# STM32F2_Controller.net
KiCad netlist of a schematic drawn in EAGLE
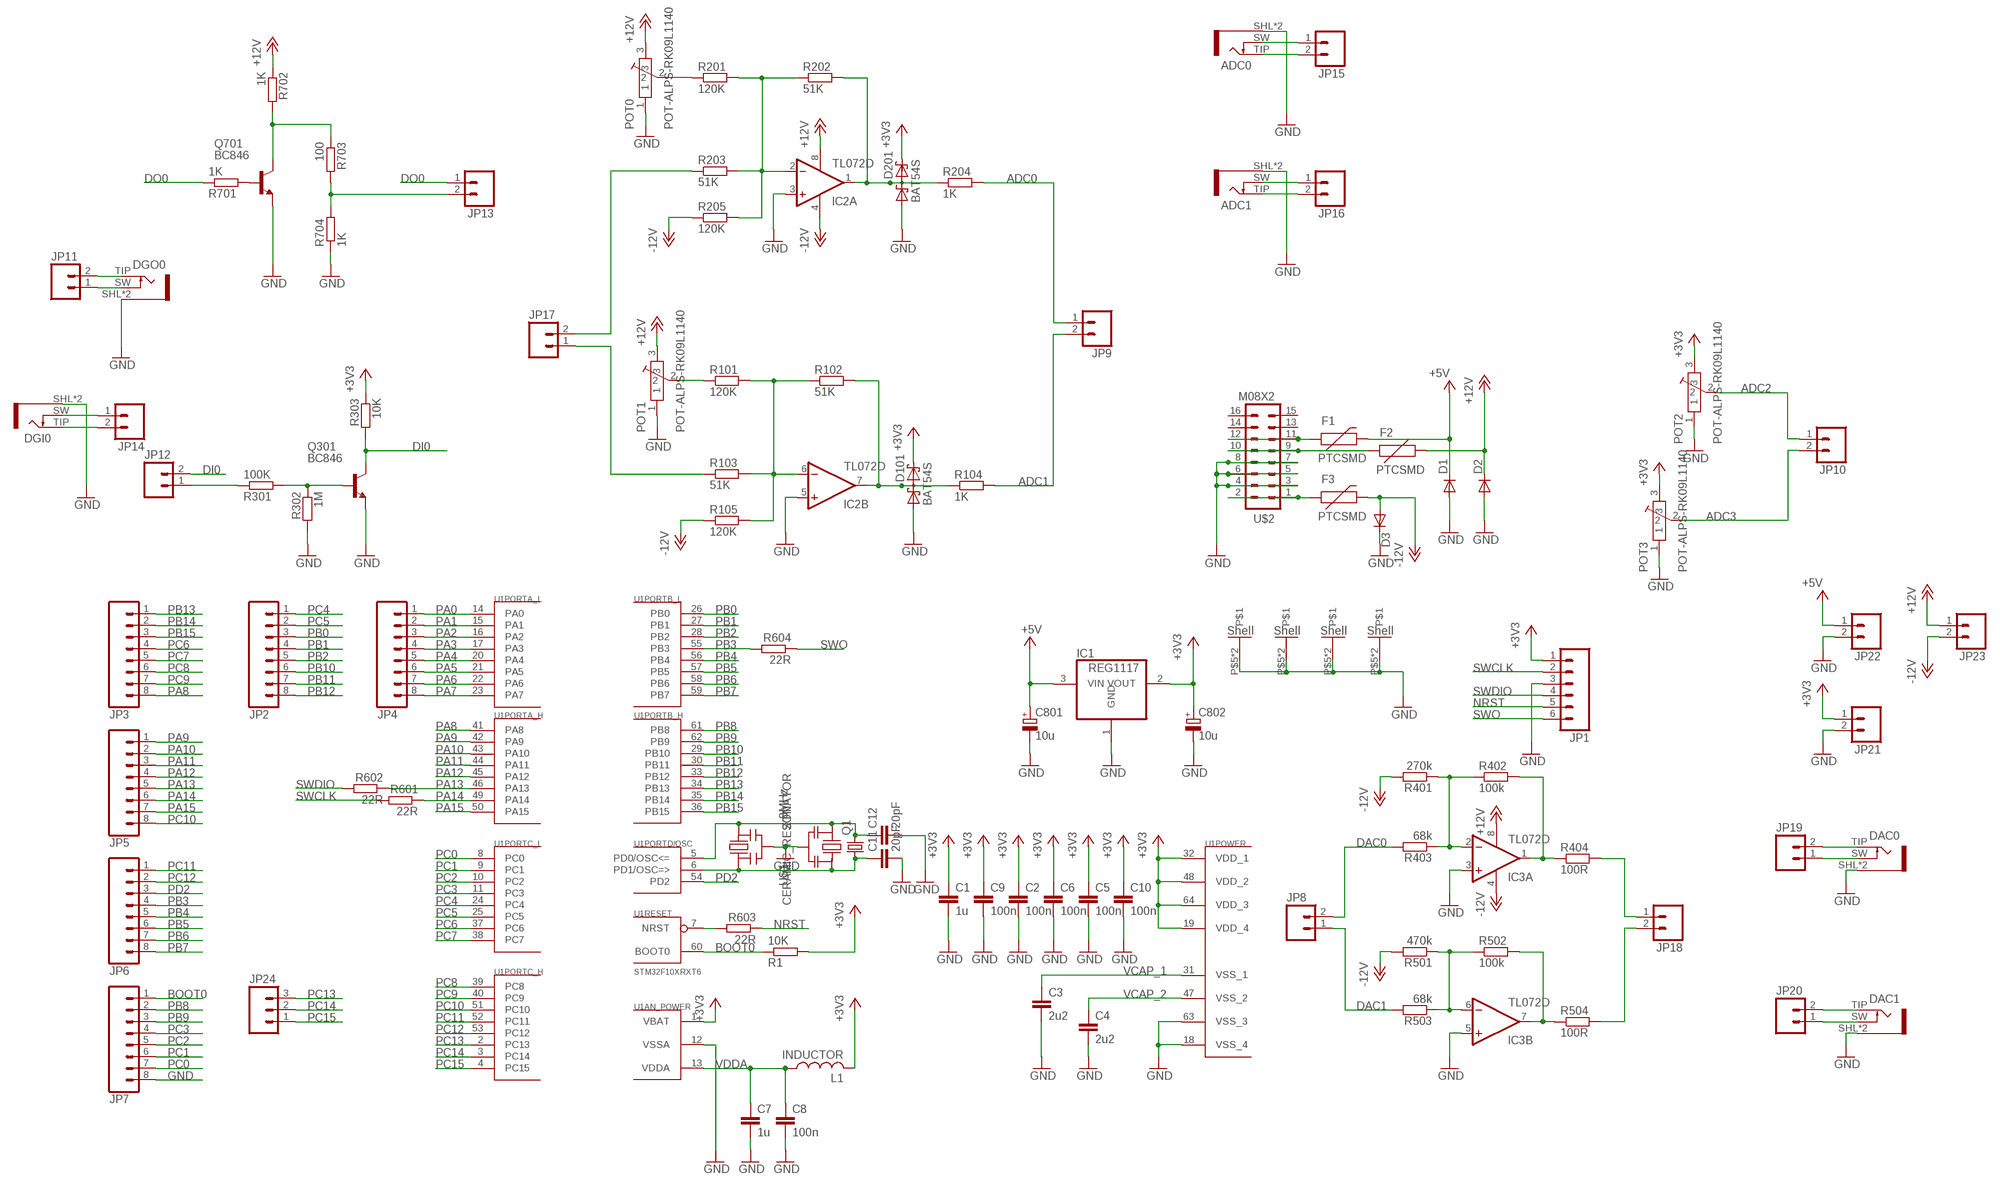
[diagram p0: schematic, sheet 1]

(export (version "E")
  (design (tool "Eeschema 10.0.6"))
  (components
    (comp (ref "ADC0")
      (value "JACK-PJ-301B")
      (footprint "eagle-import:PJ-301B")
      (libsource (lib "eagle-import") (part "JACK-PJ-301B"))
    )
    (comp (ref "ADC1")
      (value "JACK-PJ-301B")
      (footprint "eagle-import:PJ-301B")
      (libsource (lib "eagle-import") (part "JACK-PJ-301B"))
    )
    (comp (ref "C1")
      (value "1u")
      (footprint "eagle-import:C0603")
      (libsource (lib "eagle-import") (part "C-EUC0603"))
    )
    (comp (ref "C2")
      (value "100n")
      (footprint "eagle-import:C0603")
      (libsource (lib "eagle-import") (part "C-EUC0603"))
    )
    (comp (ref "C3")
      (value "2u2")
      (footprint "eagle-import:C0603")
      (libsource (lib "eagle-import") (part "C-EUC0603"))
    )
    (comp (ref "C4")
      (value "2u2")
      (footprint "eagle-import:C0603")
      (libsource (lib "eagle-import") (part "C-EUC0603"))
    )
    (comp (ref "C5")
      (value "100n")
      (footprint "eagle-import:C0603")
      (libsource (lib "eagle-import") (part "C-EUC0603"))
    )
    (comp (ref "C6")
      (value "100n")
      (footprint "eagle-import:C0603")
      (libsource (lib "eagle-import") (part "C-EUC0603"))
    )
    (comp (ref "C7")
      (value "1u")
      (footprint "eagle-import:C0603")
      (libsource (lib "eagle-import") (part "C-EUC0603"))
    )
    (comp (ref "C8")
      (value "100n")
      (footprint "eagle-import:C0603")
      (libsource (lib "eagle-import") (part "C-EUC0603"))
    )
    (comp (ref "C9")
      (value "100n")
      (footprint "eagle-import:C0603")
      (libsource (lib "eagle-import") (part "C-EUC0603"))
    )
    (comp (ref "C10")
      (value "100n")
      (footprint "eagle-import:C0603")
      (libsource (lib "eagle-import") (part "C-EUC0603"))
    )
    (comp (ref "C11")
      (value "20pF")
      (footprint "eagle-import:C0603")
      (libsource (lib "eagle-import") (part "C-EUC0603"))
    )
    (comp (ref "C12")
      (value "20pF")
      (footprint "eagle-import:C0603")
      (libsource (lib "eagle-import") (part "C-EUC0603"))
    )
    (comp (ref "C801")
      (value "10u")
      (footprint "eagle-import:PANASONIC_A")
      (libsource (lib "eagle-import") (part "CPOL-EUA"))
    )
    (comp (ref "C802")
      (value "10u")
      (footprint "eagle-import:PANASONIC_A")
      (libsource (lib "eagle-import") (part "CPOL-EUA"))
    )
    (comp (ref "D1")
      (value "DIODESMA")
      (footprint "eagle-import:SMA-DIODE")
      (libsource (lib "eagle-import") (part "DIODESMA"))
    )
    (comp (ref "D2")
      (value "DIODESMA")
      (footprint "eagle-import:SMA-DIODE")
      (libsource (lib "eagle-import") (part "DIODESMA"))
    )
    (comp (ref "D3")
      (value "DIODESMA")
      (footprint "eagle-import:SMA-DIODE")
      (libsource (lib "eagle-import") (part "DIODESMA"))
    )
    (comp (ref "D101")
      (value "BAT54S")
      (footprint "eagle-import:SOT23")
      (libsource (lib "eagle-import") (part "BAT54S"))
    )
    (comp (ref "D201")
      (value "BAT54S")
      (footprint "eagle-import:SOT23")
      (libsource (lib "eagle-import") (part "BAT54S"))
    )
    (comp (ref "DAC0")
      (value "JACK-PJ-301B")
      (footprint "eagle-import:PJ-301B")
      (libsource (lib "eagle-import") (part "JACK-PJ-301B"))
    )
    (comp (ref "DAC1")
      (value "JACK-PJ-301B")
      (footprint "eagle-import:PJ-301B")
      (libsource (lib "eagle-import") (part "JACK-PJ-301B"))
    )
    (comp (ref "DGI0")
      (value "JACK-PJ-301B")
      (footprint "eagle-import:PJ-301B")
      (libsource (lib "eagle-import") (part "JACK-PJ-301B"))
    )
    (comp (ref "DGO0")
      (value "JACK-PJ-301B")
      (footprint "eagle-import:PJ-301B")
      (libsource (lib "eagle-import") (part "JACK-PJ-301B"))
    )
    (comp (ref "F1")
      (value "PTCSMD")
      (footprint "eagle-import:PTC-1206")
      (libsource (lib "eagle-import") (part "PTCSMD"))
    )
    (comp (ref "F2")
      (value "PTCSMD")
      (footprint "eagle-import:PTC-1206")
      (libsource (lib "eagle-import") (part "PTCSMD"))
    )
    (comp (ref "F3")
      (value "PTCSMD")
      (footprint "eagle-import:PTC-1206")
      (libsource (lib "eagle-import") (part "PTCSMD"))
    )
    (comp (ref "IC1")
      (value "REG1117")
      (footprint "eagle-import:SOT223")
      (libsource (lib "eagle-import") (part "REG1117"))
    )
    (comp (ref "IC2")
      (value "TL072D")
      (footprint "eagle-import:SO08")
      (libsource (lib "eagle-import") (part "TL072D"))
    )
    (comp (ref "IC3")
      (value "TL072D")
      (footprint "eagle-import:SO08")
      (libsource (lib "eagle-import") (part "TL072D"))
    )
    (comp (ref "JP1")
      (value "M06SIP")
      (footprint "eagle-import:1X06")
      (libsource (lib "eagle-import") (part "M06SIP"))
    )
    (comp (ref "JP2")
      (value "M081X08")
      (footprint "eagle-import:1X08")
      (libsource (lib "eagle-import") (part "M081X08"))
    )
    (comp (ref "JP3")
      (value "M081X08")
      (footprint "eagle-import:1X08")
      (libsource (lib "eagle-import") (part "M081X08"))
    )
    (comp (ref "JP4")
      (value "M081X08")
      (footprint "eagle-import:1X08")
      (libsource (lib "eagle-import") (part "M081X08"))
    )
    (comp (ref "JP5")
      (value "M081X08")
      (footprint "eagle-import:1X08")
      (libsource (lib "eagle-import") (part "M081X08"))
    )
    (comp (ref "JP6")
      (value "M081X08")
      (footprint "eagle-import:1X08")
      (libsource (lib "eagle-import") (part "M081X08"))
    )
    (comp (ref "JP7")
      (value "M081X08")
      (footprint "eagle-import:1X08")
      (libsource (lib "eagle-import") (part "M081X08"))
    )
    (comp (ref "JP8")
      (value "M02PTH")
      (footprint "eagle-import:1X02")
      (libsource (lib "eagle-import") (part "M02PTH"))
    )
    (comp (ref "JP9")
      (value "M02PTH")
      (footprint "eagle-import:1X02")
      (libsource (lib "eagle-import") (part "M02PTH"))
    )
    (comp (ref "JP10")
      (value "M02PTH")
      (footprint "eagle-import:1X02")
      (libsource (lib "eagle-import") (part "M02PTH"))
    )
    (comp (ref "JP11")
      (value "M02PTH")
      (footprint "eagle-import:1X02")
      (libsource (lib "eagle-import") (part "M02PTH"))
    )
    (comp (ref "JP12")
      (value "M02PTH")
      (footprint "eagle-import:1X02")
      (libsource (lib "eagle-import") (part "M02PTH"))
    )
    (comp (ref "JP13")
      (value "M02PTH")
      (footprint "eagle-import:1X02")
      (libsource (lib "eagle-import") (part "M02PTH"))
    )
    (comp (ref "JP14")
      (value "M02PTH")
      (footprint "eagle-import:1X02")
      (libsource (lib "eagle-import") (part "M02PTH"))
    )
    (comp (ref "JP15")
      (value "M02PTH")
      (footprint "eagle-import:1X02")
      (libsource (lib "eagle-import") (part "M02PTH"))
    )
    (comp (ref "JP16")
      (value "M02PTH")
      (footprint "eagle-import:1X02")
      (libsource (lib "eagle-import") (part "M02PTH"))
    )
    (comp (ref "JP17")
      (value "M02PTH")
      (footprint "eagle-import:1X02")
      (libsource (lib "eagle-import") (part "M02PTH"))
    )
    (comp (ref "JP18")
      (value "M02PTH")
      (footprint "eagle-import:1X02")
      (libsource (lib "eagle-import") (part "M02PTH"))
    )
    (comp (ref "JP19")
      (value "M02PTH")
      (footprint "eagle-import:1X02")
      (libsource (lib "eagle-import") (part "M02PTH"))
    )
    (comp (ref "JP20")
      (value "M02PTH")
      (footprint "eagle-import:1X02")
      (libsource (lib "eagle-import") (part "M02PTH"))
    )
    (comp (ref "JP21")
      (value "M02PTH")
      (footprint "eagle-import:1X02")
      (libsource (lib "eagle-import") (part "M02PTH"))
    )
    (comp (ref "JP22")
      (value "M02PTH")
      (footprint "eagle-import:1X02")
      (libsource (lib "eagle-import") (part "M02PTH"))
    )
    (comp (ref "JP23")
      (value "M02PTH")
      (footprint "eagle-import:1X02")
      (libsource (lib "eagle-import") (part "M02PTH"))
    )
    (comp (ref "JP24")
      (value "M03PTH")
      (footprint "eagle-import:1X03")
      (libsource (lib "eagle-import") (part "M03PTH"))
    )
    (comp (ref "L1")
      (value "INDUCTOR")
      (footprint "eagle-import:0603")
      (libsource (lib "eagle-import") (part "INDUCTOR"))
    )
    (comp (ref "POT0")
      (value "POT-ALPS-RK09L1140")
      (footprint "eagle-import:POT-ALPS-RK09L1140")
      (libsource (lib "eagle-import") (part "POT-ALPS-RK09L1140"))
    )
    (comp (ref "POT1")
      (value "POT-ALPS-RK09L1140")
      (footprint "eagle-import:POT-ALPS-RK09L1140")
      (libsource (lib "eagle-import") (part "POT-ALPS-RK09L1140"))
    )
    (comp (ref "POT2")
      (value "POT-ALPS-RK09L1140")
      (footprint "eagle-import:POT-ALPS-RK09L1140")
      (libsource (lib "eagle-import") (part "POT-ALPS-RK09L1140"))
    )
    (comp (ref "POT3")
      (value "POT-ALPS-RK09L1140")
      (footprint "eagle-import:POT-ALPS-RK09L1140")
      (libsource (lib "eagle-import") (part "POT-ALPS-RK09L1140"))
    )
    (comp (ref "Q1")
      (value "CRYSTALHC49UP")
      (footprint "eagle-import:HC49UP")
      (libsource (lib "eagle-import") (part "CRYSTALHC49UP"))
    )
    (comp (ref "Q301")
      (value "BC846")
      (footprint "eagle-import:SOT23")
      (libsource (lib "eagle-import") (part "BC846"))
    )
    (comp (ref "Q701")
      (value "BC846")
      (footprint "eagle-import:SOT23")
      (libsource (lib "eagle-import") (part "BC846"))
    )
    (comp (ref "R1")
      (value "10K")
      (footprint "eagle-import:R0603")
      (libsource (lib "eagle-import") (part "R-EU_R0603"))
    )
    (comp (ref "R101")
      (value "120K")
      (footprint "eagle-import:R0603")
      (libsource (lib "eagle-import") (part "R-EU_R0603"))
    )
    (comp (ref "R102")
      (value "51K")
      (footprint "eagle-import:R0603")
      (libsource (lib "eagle-import") (part "R-EU_R0603"))
    )
    (comp (ref "R103")
      (value "51K")
      (footprint "eagle-import:R0603")
      (libsource (lib "eagle-import") (part "R-EU_R0603"))
    )
    (comp (ref "R104")
      (value "1K")
      (footprint "eagle-import:R0603")
      (libsource (lib "eagle-import") (part "R-EU_R0603"))
    )
    (comp (ref "R105")
      (value "120K")
      (footprint "eagle-import:R0603")
      (libsource (lib "eagle-import") (part "R-EU_R0603"))
    )
    (comp (ref "R201")
      (value "120K")
      (footprint "eagle-import:R0603")
      (libsource (lib "eagle-import") (part "R-EU_R0603"))
    )
    (comp (ref "R202")
      (value "51K")
      (footprint "eagle-import:R0603")
      (libsource (lib "eagle-import") (part "R-EU_R0603"))
    )
    (comp (ref "R203")
      (value "51K")
      (footprint "eagle-import:R0603")
      (libsource (lib "eagle-import") (part "R-EU_R0603"))
    )
    (comp (ref "R204")
      (value "1K")
      (footprint "eagle-import:R0603")
      (libsource (lib "eagle-import") (part "R-EU_R0603"))
    )
    (comp (ref "R205")
      (value "120K")
      (footprint "eagle-import:R0603")
      (libsource (lib "eagle-import") (part "R-EU_R0603"))
    )
    (comp (ref "R301")
      (value "100K")
      (footprint "eagle-import:R0603")
      (libsource (lib "eagle-import") (part "R-EU_R0603"))
    )
    (comp (ref "R302")
      (value "1M")
      (footprint "eagle-import:R0603")
      (libsource (lib "eagle-import") (part "R-EU_R0603"))
    )
    (comp (ref "R303")
      (value "10K")
      (footprint "eagle-import:R0603")
      (libsource (lib "eagle-import") (part "R-EU_R0603"))
    )
    (comp (ref "R401")
      (value "270k")
      (footprint "eagle-import:R0603")
      (libsource (lib "eagle-import") (part "R-EU_R0603"))
    )
    (comp (ref "R402")
      (value "100k")
      (footprint "eagle-import:R0603")
      (libsource (lib "eagle-import") (part "R-EU_R0603"))
    )
    (comp (ref "R403")
      (value "68k")
      (footprint "eagle-import:R0603")
      (libsource (lib "eagle-import") (part "R-EU_R0603"))
    )
    (comp (ref "R404")
      (value "100R")
      (footprint "eagle-import:R0603")
      (libsource (lib "eagle-import") (part "R-EU_R0603"))
    )
    (comp (ref "R501")
      (value "470k")
      (footprint "eagle-import:R0603")
      (libsource (lib "eagle-import") (part "R-EU_R0603"))
    )
    (comp (ref "R502")
      (value "100k")
      (footprint "eagle-import:R0603")
      (libsource (lib "eagle-import") (part "R-EU_R0603"))
    )
    (comp (ref "R503")
      (value "68k")
      (footprint "eagle-import:R0603")
      (libsource (lib "eagle-import") (part "R-EU_R0603"))
    )
    (comp (ref "R504")
      (value "100R")
      (footprint "eagle-import:R0603")
      (libsource (lib "eagle-import") (part "R-EU_R0603"))
    )
    (comp (ref "R601")
      (value "22R")
      (footprint "eagle-import:R0603")
      (libsource (lib "eagle-import") (part "R-EU_R0603"))
    )
    (comp (ref "R602")
      (value "22R")
      (footprint "eagle-import:R0603")
      (libsource (lib "eagle-import") (part "R-EU_R0603"))
    )
    (comp (ref "R603")
      (value "22R")
      (footprint "eagle-import:R0603")
      (libsource (lib "eagle-import") (part "R-EU_R0603"))
    )
    (comp (ref "R604")
      (value "22R")
      (footprint "eagle-import:R0603")
      (libsource (lib "eagle-import") (part "R-EU_R0603"))
    )
    (comp (ref "R701")
      (value "1K")
      (footprint "eagle-import:R0603")
      (libsource (lib "eagle-import") (part "R-EU_R0603"))
    )
    (comp (ref "R702")
      (value "1K")
      (footprint "eagle-import:R0603")
      (libsource (lib "eagle-import") (part "R-EU_R0603"))
    )
    (comp (ref "R703")
      (value "100")
      (footprint "eagle-import:R0603")
      (libsource (lib "eagle-import") (part "R-EU_R0603"))
    )
    (comp (ref "R704")
      (value "1K")
      (footprint "eagle-import:R0603")
      (libsource (lib "eagle-import") (part "R-EU_R0603"))
    )
    (comp (ref "U$1")
      (value "8MHz")
      (footprint "eagle-import:CSTCR-G")
      (libsource (lib "eagle-import") (part "CERMOSCILL-CSTCRG"))
    )
    (comp (ref "U$2")
      (value "M08X2")
      (footprint "eagle-import:2X8")
      (libsource (lib "eagle-import") (part "M08X2"))
    )
    (comp (ref "U1")
      (value "STM32F10XRXT6")
      (footprint "eagle-import:TQFP64")
      (libsource (lib "eagle-import") (part "STM32F10XRXT6"))
    )
    (comp (ref "ZTT")
      (value "CERAMIC_RESONATOR")
      (footprint "eagle-import:CSTCE_G_A")
      (libsource (lib "eagle-import") (part "CERAMIC_RESONATOR"))
    )
  )
  (nets
    (net (code "1") (name "+3V3") (class "Default")
      (node (ref "C1") (pin "1") (pinfunction "1_1") (pintype "passive"))
      (node (ref "C10") (pin "1") (pinfunction "1_1") (pintype "passive"))
      (node (ref "C2") (pin "1") (pinfunction "1_1") (pintype "passive"))
      (node (ref "C5") (pin "1") (pinfunction "1_1") (pintype "passive"))
      (node (ref "C6") (pin "1") (pinfunction "1_1") (pintype "passive"))
      (node (ref "C802") (pin "+") (pinfunction "+_+") (pintype "passive"))
      (node (ref "C9") (pin "1") (pinfunction "1_1") (pintype "passive"))
      (node (ref "D101") (pin "2") (pinfunction "C2_2") (pintype "passive"))
      (node (ref "D201") (pin "2") (pinfunction "C2_2") (pintype "passive"))
      (node (ref "IC1") (pin "2") (pinfunction "VOUT_2") (pintype "output"))
      (node (ref "JP1") (pin "1") (pinfunction "1_1") (pintype "passive"))
      (node (ref "JP21") (pin "1") (pinfunction "1_1") (pintype "passive"))
      (node (ref "L1") (pin "2") (pinfunction "2_2") (pintype "passive"))
      (node (ref "POT2") (pin "3") (pinfunction "3_3") (pintype "bidirectional"))
      (node (ref "POT3") (pin "3") (pinfunction "3_3") (pintype "bidirectional"))
      (node (ref "R1") (pin "2") (pinfunction "2_2") (pintype "passive"))
      (node (ref "R303") (pin "1") (pinfunction "1_1") (pintype "passive"))
      (node (ref "U1") (pin "1") (pinfunction "VBAT_1") (pintype "power_in"))
      (node (ref "U1") (pin "19") (pinfunction "VDD_4_19") (pintype "power_in"))
      (node (ref "U1") (pin "32") (pinfunction "VDD_1_32") (pintype "power_in"))
      (node (ref "U1") (pin "48") (pinfunction "VDD_2_48") (pintype "power_in"))
      (node (ref "U1") (pin "64") (pinfunction "VDD_3_64") (pintype "power_in"))
    )
    (net (code "2") (name "+5V") (class "Default")
      (node (ref "C801") (pin "+") (pinfunction "+_+") (pintype "passive"))
      (node (ref "D1") (pin "C") (pinfunction "C_C") (pintype "passive"))
      (node (ref "F1") (pin "2") (pinfunction "2_2") (pintype "bidirectional"))
      (node (ref "IC1") (pin "3") (pinfunction "VIN_3") (pintype "input"))
      (node (ref "JP22") (pin "1") (pinfunction "1_1") (pintype "passive"))
    )
    (net (code "3") (name "+12V") (class "Default")
      (node (ref "D2") (pin "C") (pinfunction "C_C") (pintype "passive"))
      (node (ref "F2") (pin "2") (pinfunction "2_2") (pintype "bidirectional"))
      (node (ref "IC2") (pin "8") (pinfunction "V+_8") (pintype "power_in"))
      (node (ref "IC3") (pin "8") (pinfunction "V+_8") (pintype "power_in"))
      (node (ref "JP23") (pin "1") (pinfunction "1_1") (pintype "passive"))
      (node (ref "POT0") (pin "3") (pinfunction "3_3") (pintype "bidirectional"))
      (node (ref "POT1") (pin "3") (pinfunction "3_3") (pintype "bidirectional"))
      (node (ref "R702") (pin "1") (pinfunction "1_1") (pintype "passive"))
    )
    (net (code "4") (name "-12V") (class "Default")
      (node (ref "D3") (pin "A") (pinfunction "A_A") (pintype "passive"))
      (node (ref "F3") (pin "2") (pinfunction "2_2") (pintype "bidirectional"))
      (node (ref "IC2") (pin "4") (pinfunction "V-_4") (pintype "power_in"))
      (node (ref "IC3") (pin "4") (pinfunction "V-_4") (pintype "power_in"))
      (node (ref "JP23") (pin "2") (pinfunction "2_2") (pintype "passive"))
      (node (ref "R105") (pin "1") (pinfunction "1_1") (pintype "passive"))
      (node (ref "R205") (pin "1") (pinfunction "1_1") (pintype "passive"))
      (node (ref "R401") (pin "2") (pinfunction "2_2") (pintype "passive"))
      (node (ref "R501") (pin "2") (pinfunction "2_2") (pintype "passive"))
    )
    (net (code "5") (name "/ADC0") (class "Default")
      (node (ref "JP9") (pin "1") (pinfunction "1_1") (pintype "passive"))
      (node (ref "R204") (pin "2") (pinfunction "2_2") (pintype "passive"))
    )
    (net (code "6") (name "/ADC1") (class "Default")
      (node (ref "JP9") (pin "2") (pinfunction "2_2") (pintype "passive"))
      (node (ref "R104") (pin "2") (pinfunction "2_2") (pintype "passive"))
    )
    (net (code "7") (name "/ADC2") (class "Default")
      (node (ref "JP10") (pin "1") (pinfunction "1_1") (pintype "passive"))
      (node (ref "POT2") (pin "2") (pinfunction "2_2") (pintype "bidirectional"))
    )
    (net (code "8") (name "/ADC3") (class "Default")
      (node (ref "JP10") (pin "2") (pinfunction "2_2") (pintype "passive"))
      (node (ref "POT3") (pin "2") (pinfunction "2_2") (pintype "bidirectional"))
    )
    (net (code "9") (name "/BOOT0") (class "Default")
      (node (ref "JP7") (pin "1") (pinfunction "1_1") (pintype "passive"))
      (node (ref "R1") (pin "1") (pinfunction "1_1") (pintype "passive"))
      (node (ref "U1") (pin "60") (pinfunction "BOOT0_60") (pintype "input"))
    )
    (net (code "10") (name "/DAC0") (class "Default")
      (node (ref "JP8") (pin "2") (pinfunction "2_2") (pintype "passive"))
      (node (ref "R403") (pin "2") (pinfunction "2_2") (pintype "passive"))
    )
    (net (code "11") (name "/DAC1") (class "Default")
      (node (ref "JP8") (pin "1") (pinfunction "1_1") (pintype "passive"))
      (node (ref "R503") (pin "2") (pinfunction "2_2") (pintype "passive"))
    )
    (net (code "12") (name "/DI0") (class "Default")
      (node (ref "JP12") (pin "2") (pinfunction "2_2") (pintype "passive"))
      (node (ref "Q301") (pin "3") (pinfunction "C_3") (pintype "passive"))
      (node (ref "R303") (pin "2") (pinfunction "2_2") (pintype "passive"))
    )
    (net (code "13") (name "/DO0") (class "Default")
      (node (ref "JP13") (pin "1") (pinfunction "1_1") (pintype "passive"))
      (node (ref "R701") (pin "1") (pinfunction "1_1") (pintype "passive"))
    )
    (net (code "14") (name "/NRST") (class "Default")
      (node (ref "JP1") (pin "5") (pinfunction "5_5") (pintype "passive"))
      (node (ref "R603") (pin "1") (pinfunction "1_1") (pintype "passive"))
    )
    (net (code "15") (name "/PA0") (class "Default")
      (node (ref "JP4") (pin "1") (pinfunction "1_1") (pintype "passive"))
      (node (ref "U1") (pin "14") (pinfunction "PA0_14") (pintype "bidirectional"))
    )
    (net (code "16") (name "/PA1") (class "Default")
      (node (ref "JP4") (pin "2") (pinfunction "2_2") (pintype "passive"))
      (node (ref "U1") (pin "15") (pinfunction "PA1_15") (pintype "bidirectional"))
    )
    (net (code "17") (name "/PA2") (class "Default")
      (node (ref "JP4") (pin "3") (pinfunction "3_3") (pintype "passive"))
      (node (ref "U1") (pin "16") (pinfunction "PA2_16") (pintype "bidirectional"))
    )
    (net (code "18") (name "/PA3") (class "Default")
      (node (ref "JP4") (pin "4") (pinfunction "4_4") (pintype "passive"))
      (node (ref "U1") (pin "17") (pinfunction "PA3_17") (pintype "bidirectional"))
    )
    (net (code "19") (name "/PA4") (class "Default")
      (node (ref "JP4") (pin "5") (pinfunction "5_5") (pintype "passive"))
      (node (ref "U1") (pin "20") (pinfunction "PA4_20") (pintype "bidirectional"))
    )
    (net (code "20") (name "/PA5") (class "Default")
      (node (ref "JP4") (pin "6") (pinfunction "6_6") (pintype "passive"))
      (node (ref "U1") (pin "21") (pinfunction "PA5_21") (pintype "bidirectional"))
    )
    (net (code "21") (name "/PA6") (class "Default")
      (node (ref "JP4") (pin "7") (pinfunction "7_7") (pintype "passive"))
      (node (ref "U1") (pin "22") (pinfunction "PA6_22") (pintype "bidirectional"))
    )
    (net (code "22") (name "/PA7") (class "Default")
      (node (ref "JP4") (pin "8") (pinfunction "8_8") (pintype "passive"))
      (node (ref "U1") (pin "23") (pinfunction "PA7_23") (pintype "bidirectional"))
    )
    (net (code "23") (name "/PA8") (class "Default")
      (node (ref "JP3") (pin "8") (pinfunction "8_8") (pintype "passive"))
      (node (ref "U1") (pin "41") (pinfunction "PA8_41") (pintype "bidirectional"))
    )
    (net (code "24") (name "/PA9") (class "Default")
      (node (ref "JP5") (pin "1") (pinfunction "1_1") (pintype "passive"))
      (node (ref "U1") (pin "42") (pinfunction "PA9_42") (pintype "bidirectional"))
    )
    (net (code "25") (name "/PA10") (class "Default")
      (node (ref "JP5") (pin "2") (pinfunction "2_2") (pintype "passive"))
      (node (ref "U1") (pin "43") (pinfunction "PA10_43") (pintype "bidirectional"))
    )
    (net (code "26") (name "/PA11") (class "Default")
      (node (ref "JP5") (pin "3") (pinfunction "3_3") (pintype "passive"))
      (node (ref "U1") (pin "44") (pinfunction "PA11_44") (pintype "bidirectional"))
    )
    (net (code "27") (name "/PA12") (class "Default")
      (node (ref "JP5") (pin "4") (pinfunction "4_4") (pintype "passive"))
      (node (ref "U1") (pin "45") (pinfunction "PA12_45") (pintype "bidirectional"))
    )
    (net (code "28") (name "/PA13") (class "Default")
      (node (ref "JP5") (pin "5") (pinfunction "5_5") (pintype "passive"))
      (node (ref "R602") (pin "1") (pinfunction "1_1") (pintype "passive"))
      (node (ref "U1") (pin "46") (pinfunction "PA13_46") (pintype "bidirectional"))
    )
    (net (code "29") (name "/PA14") (class "Default")
      (node (ref "JP5") (pin "6") (pinfunction "6_6") (pintype "passive"))
      (node (ref "R601") (pin "1") (pinfunction "1_1") (pintype "passive"))
      (node (ref "U1") (pin "49") (pinfunction "PA14_49") (pintype "bidirectional"))
    )
    (net (code "30") (name "/PA15") (class "Default")
      (node (ref "JP5") (pin "7") (pinfunction "7_7") (pintype "passive"))
      (node (ref "U1") (pin "50") (pinfunction "PA15_50") (pintype "bidirectional"))
    )
    (net (code "31") (name "/PB0") (class "Default")
      (node (ref "JP2") (pin "3") (pinfunction "3_3") (pintype "passive"))
      (node (ref "U1") (pin "26") (pinfunction "PB0_26") (pintype "bidirectional"))
    )
    (net (code "32") (name "/PB1") (class "Default")
      (node (ref "JP2") (pin "4") (pinfunction "4_4") (pintype "passive"))
      (node (ref "U1") (pin "27") (pinfunction "PB1_27") (pintype "bidirectional"))
    )
    (net (code "33") (name "/PB2") (class "Default")
      (node (ref "JP2") (pin "5") (pinfunction "5_5") (pintype "passive"))
      (node (ref "U1") (pin "28") (pinfunction "PB2_28") (pintype "bidirectional"))
    )
    (net (code "34") (name "/PB3") (class "Default")
      (node (ref "JP6") (pin "4") (pinfunction "4_4") (pintype "passive"))
      (node (ref "R604") (pin "2") (pinfunction "2_2") (pintype "passive"))
      (node (ref "U1") (pin "55") (pinfunction "PB3_55") (pintype "bidirectional"))
    )
    (net (code "35") (name "/PB4") (class "Default")
      (node (ref "JP6") (pin "5") (pinfunction "5_5") (pintype "passive"))
      (node (ref "U1") (pin "56") (pinfunction "PB4_56") (pintype "bidirectional"))
    )
    (net (code "36") (name "/PB5") (class "Default")
      (node (ref "JP6") (pin "6") (pinfunction "6_6") (pintype "passive"))
      (node (ref "U1") (pin "57") (pinfunction "PB5_57") (pintype "bidirectional"))
    )
    (net (code "37") (name "/PB6") (class "Default")
      (node (ref "JP6") (pin "7") (pinfunction "7_7") (pintype "passive"))
      (node (ref "U1") (pin "58") (pinfunction "PB6_58") (pintype "bidirectional"))
    )
    (net (code "38") (name "/PB7") (class "Default")
      (node (ref "JP6") (pin "8") (pinfunction "8_8") (pintype "passive"))
      (node (ref "U1") (pin "59") (pinfunction "PB7_59") (pintype "bidirectional"))
    )
    (net (code "39") (name "/PB8") (class "Default")
      (node (ref "JP7") (pin "2") (pinfunction "2_2") (pintype "passive"))
      (node (ref "U1") (pin "61") (pinfunction "PB8_61") (pintype "bidirectional"))
    )
    (net (code "40") (name "/PB9") (class "Default")
      (node (ref "JP7") (pin "3") (pinfunction "3_3") (pintype "passive"))
      (node (ref "U1") (pin "62") (pinfunction "PB9_62") (pintype "bidirectional"))
    )
    (net (code "41") (name "/PB10") (class "Default")
      (node (ref "JP2") (pin "6") (pinfunction "6_6") (pintype "passive"))
      (node (ref "U1") (pin "29") (pinfunction "PB10_29") (pintype "bidirectional"))
    )
    (net (code "42") (name "/PB11") (class "Default")
      (node (ref "JP2") (pin "7") (pinfunction "7_7") (pintype "passive"))
      (node (ref "U1") (pin "30") (pinfunction "PB11_30") (pintype "bidirectional"))
    )
    (net (code "43") (name "/PB12") (class "Default")
      (node (ref "JP2") (pin "8") (pinfunction "8_8") (pintype "passive"))
      (node (ref "U1") (pin "33") (pinfunction "PB12_33") (pintype "bidirectional"))
    )
    (net (code "44") (name "/PB13") (class "Default")
      (node (ref "JP3") (pin "1") (pinfunction "1_1") (pintype "passive"))
      (node (ref "U1") (pin "34") (pinfunction "PB13_34") (pintype "bidirectional"))
    )
    (net (code "45") (name "/PB14") (class "Default")
      (node (ref "JP3") (pin "2") (pinfunction "2_2") (pintype "passive"))
      (node (ref "U1") (pin "35") (pinfunction "PB14_35") (pintype "bidirectional"))
    )
    (net (code "46") (name "/PB15") (class "Default")
      (node (ref "JP3") (pin "3") (pinfunction "3_3") (pintype "passive"))
      (node (ref "U1") (pin "36") (pinfunction "PB15_36") (pintype "bidirectional"))
    )
    (net (code "47") (name "/PC0") (class "Default")
      (node (ref "JP7") (pin "7") (pinfunction "7_7") (pintype "passive"))
      (node (ref "U1") (pin "8") (pinfunction "PC0_8") (pintype "bidirectional"))
    )
    (net (code "48") (name "/PC1") (class "Default")
      (node (ref "JP7") (pin "6") (pinfunction "6_6") (pintype "passive"))
      (node (ref "U1") (pin "9") (pinfunction "PC1_9") (pintype "bidirectional"))
    )
    (net (code "49") (name "/PC2") (class "Default")
      (node (ref "JP7") (pin "5") (pinfunction "5_5") (pintype "passive"))
      (node (ref "U1") (pin "10") (pinfunction "PC2_10") (pintype "bidirectional"))
    )
    (net (code "50") (name "/PC3") (class "Default")
      (node (ref "JP7") (pin "4") (pinfunction "4_4") (pintype "passive"))
      (node (ref "U1") (pin "11") (pinfunction "PC3_11") (pintype "bidirectional"))
    )
    (net (code "51") (name "/PC4") (class "Default")
      (node (ref "JP2") (pin "1") (pinfunction "1_1") (pintype "passive"))
      (node (ref "U1") (pin "24") (pinfunction "PC4_24") (pintype "bidirectional"))
    )
    (net (code "52") (name "/PC5") (class "Default")
      (node (ref "JP2") (pin "2") (pinfunction "2_2") (pintype "passive"))
      (node (ref "U1") (pin "25") (pinfunction "PC5_25") (pintype "bidirectional"))
    )
    (net (code "53") (name "/PC6") (class "Default")
      (node (ref "JP3") (pin "4") (pinfunction "4_4") (pintype "passive"))
      (node (ref "U1") (pin "37") (pinfunction "PC6_37") (pintype "bidirectional"))
    )
    (net (code "54") (name "/PC7") (class "Default")
      (node (ref "JP3") (pin "5") (pinfunction "5_5") (pintype "passive"))
      (node (ref "U1") (pin "38") (pinfunction "PC7_38") (pintype "bidirectional"))
    )
    (net (code "55") (name "/PC8") (class "Default")
      (node (ref "JP3") (pin "6") (pinfunction "6_6") (pintype "passive"))
      (node (ref "U1") (pin "39") (pinfunction "PC8_39") (pintype "bidirectional"))
    )
    (net (code "56") (name "/PC9") (class "Default")
      (node (ref "JP3") (pin "7") (pinfunction "7_7") (pintype "passive"))
      (node (ref "U1") (pin "40") (pinfunction "PC9_40") (pintype "bidirectional"))
    )
    (net (code "57") (name "/PC10") (class "Default")
      (node (ref "JP5") (pin "8") (pinfunction "8_8") (pintype "passive"))
      (node (ref "U1") (pin "51") (pinfunction "PC10_51") (pintype "bidirectional"))
    )
    (net (code "58") (name "/PC11") (class "Default")
      (node (ref "JP6") (pin "1") (pinfunction "1_1") (pintype "passive"))
      (node (ref "U1") (pin "52") (pinfunction "PC11_52") (pintype "bidirectional"))
    )
    (net (code "59") (name "/PC12") (class "Default")
      (node (ref "JP6") (pin "2") (pinfunction "2_2") (pintype "passive"))
      (node (ref "U1") (pin "53") (pinfunction "PC12_53") (pintype "bidirectional"))
    )
    (net (code "60") (name "/PC13") (class "Default")
      (node (ref "JP24") (pin "3") (pinfunction "3_3") (pintype "passive"))
      (node (ref "U1") (pin "2") (pinfunction "PC13_2") (pintype "bidirectional"))
    )
    (net (code "61") (name "/PC14") (class "Default")
      (node (ref "JP24") (pin "2") (pinfunction "2_2") (pintype "passive"))
      (node (ref "U1") (pin "3") (pinfunction "PC14_3") (pintype "bidirectional"))
    )
    (net (code "62") (name "/PC15") (class "Default")
      (node (ref "JP24") (pin "1") (pinfunction "1_1") (pintype "passive"))
      (node (ref "U1") (pin "4") (pinfunction "PC15_4") (pintype "bidirectional"))
    )
    (net (code "63") (name "/PD2") (class "Default")
      (node (ref "JP6") (pin "3") (pinfunction "3_3") (pintype "passive"))
      (node (ref "U1") (pin "54") (pinfunction "PD2_54") (pintype "bidirectional"))
    )
    (net (code "64") (name "/SWCLK") (class "Default")
      (node (ref "JP1") (pin "2") (pinfunction "2_2") (pintype "passive"))
      (node (ref "R601") (pin "2") (pinfunction "2_2") (pintype "passive"))
    )
    (net (code "65") (name "/SWDIO") (class "Default")
      (node (ref "JP1") (pin "4") (pinfunction "4_4") (pintype "passive"))
      (node (ref "R602") (pin "2") (pinfunction "2_2") (pintype "passive"))
    )
    (net (code "66") (name "/SWO") (class "Default")
      (node (ref "JP1") (pin "6") (pinfunction "6_6") (pintype "passive"))
      (node (ref "R604") (pin "1") (pinfunction "1_1") (pintype "passive"))
    )
    (net (code "67") (name "/VCAP_1") (class "Default")
      (node (ref "C3") (pin "1") (pinfunction "1_1") (pintype "passive"))
      (node (ref "U1") (pin "31") (pinfunction "VSS_1_31") (pintype "power_in"))
    )
    (net (code "68") (name "/VCAP_2") (class "Default")
      (node (ref "C4") (pin "1") (pinfunction "1_1") (pintype "passive"))
      (node (ref "U1") (pin "47") (pinfunction "VSS_2_47") (pintype "power_in"))
    )
    (net (code "69") (name "/VDDA") (class "Default")
      (node (ref "C7") (pin "1") (pinfunction "1_1") (pintype "passive"))
      (node (ref "C8") (pin "1") (pinfunction "1_1") (pintype "passive"))
      (node (ref "L1") (pin "1") (pinfunction "1_1") (pintype "passive"))
      (node (ref "U1") (pin "13") (pinfunction "VDDA_13") (pintype "power_in"))
    )
    (net (code "70") (name "GND") (class "Default")
      (node (ref "ADC0") (pin "SHL") (pinfunction "SLEEVE_SHL") (pintype "passive"))
      (node (ref "ADC0") (pin "SLV") (pinfunction "SLEEVE_SLV") (pintype "passive"))
      (node (ref "ADC1") (pin "SHL") (pinfunction "SLEEVE_SHL") (pintype "passive"))
      (node (ref "ADC1") (pin "SLV") (pinfunction "SLEEVE_SLV") (pintype "passive"))
      (node (ref "C1") (pin "2") (pinfunction "2_2") (pintype "passive"))
      (node (ref "C10") (pin "2") (pinfunction "2_2") (pintype "passive"))
      (node (ref "C11") (pin "2") (pinfunction "2_2") (pintype "passive"))
      (node (ref "C12") (pin "2") (pinfunction "2_2") (pintype "passive"))
      (node (ref "C2") (pin "2") (pinfunction "2_2") (pintype "passive"))
      (node (ref "C3") (pin "2") (pinfunction "2_2") (pintype "passive"))
      (node (ref "C4") (pin "2") (pinfunction "2_2") (pintype "passive"))
      (node (ref "C5") (pin "2") (pinfunction "2_2") (pintype "passive"))
      (node (ref "C6") (pin "2") (pinfunction "2_2") (pintype "passive"))
      (node (ref "C7") (pin "2") (pinfunction "2_2") (pintype "passive"))
      (node (ref "C8") (pin "2") (pinfunction "2_2") (pintype "passive"))
      (node (ref "C801") (pin "-") (pinfunction "-_-") (pintype "passive"))
      (node (ref "C802") (pin "-") (pinfunction "-_-") (pintype "passive"))
      (node (ref "C9") (pin "2") (pinfunction "2_2") (pintype "passive"))
      (node (ref "D1") (pin "A") (pinfunction "A_A") (pintype "passive"))
      (node (ref "D101") (pin "1") (pinfunction "A1_1") (pintype "passive"))
      (node (ref "D2") (pin "A") (pinfunction "A_A") (pintype "passive"))
      (node (ref "D201") (pin "1") (pinfunction "A1_1") (pintype "passive"))
      (node (ref "D3") (pin "C") (pinfunction "C_C") (pintype "passive"))
      (node (ref "DAC0") (pin "SHL") (pinfunction "SLEEVE_SHL") (pintype "passive"))
      (node (ref "DAC0") (pin "SLV") (pinfunction "SLEEVE_SLV") (pintype "passive"))
      (node (ref "DAC1") (pin "SHL") (pinfunction "SLEEVE_SHL") (pintype "passive"))
      (node (ref "DAC1") (pin "SLV") (pinfunction "SLEEVE_SLV") (pintype "passive"))
      (node (ref "DGI0") (pin "SHL") (pinfunction "SLEEVE_SHL") (pintype "passive"))
      (node (ref "DGI0") (pin "SLV") (pinfunction "SLEEVE_SLV") (pintype "passive"))
      (node (ref "DGO0") (pin "SHL") (pinfunction "SLEEVE_SHL") (pintype "passive"))
      (node (ref "DGO0") (pin "SLV") (pinfunction "SLEEVE_SLV") (pintype "passive"))
      (node (ref "IC1") (pin "1") (pinfunction "GND_1") (pintype "power_in"))
      (node (ref "IC2") (pin "3") (pinfunction "+IN_3") (pintype "input"))
      (node (ref "IC2") (pin "5") (pinfunction "+IN_5") (pintype "input"))
      (node (ref "IC3") (pin "3") (pinfunction "+IN_3") (pintype "input"))
      (node (ref "IC3") (pin "5") (pinfunction "+IN_5") (pintype "input"))
      (node (ref "JP1") (pin "3") (pinfunction "3_3") (pintype "passive"))
      (node (ref "JP21") (pin "2") (pinfunction "2_2") (pintype "passive"))
      (node (ref "JP22") (pin "2") (pinfunction "2_2") (pintype "passive"))
      (node (ref "JP7") (pin "8") (pinfunction "8_8") (pintype "passive"))
      (node (ref "POT0") (pin "1") (pinfunction "1_1") (pintype "bidirectional"))
      (node (ref "POT0") (pin "P$5") (pinfunction "P$1_P$5") (pintype "bidirectional"))
      (node (ref "POT0") (pin "P$6") (pinfunction "P$1_P$6") (pintype "bidirectional"))
      (node (ref "POT1") (pin "1") (pinfunction "1_1") (pintype "bidirectional"))
      (node (ref "POT1") (pin "P$5") (pinfunction "P$1_P$5") (pintype "bidirectional"))
      (node (ref "POT1") (pin "P$6") (pinfunction "P$1_P$6") (pintype "bidirectional"))
      (node (ref "POT2") (pin "1") (pinfunction "1_1") (pintype "bidirectional"))
      (node (ref "POT2") (pin "P$5") (pinfunction "P$1_P$5") (pintype "bidirectional"))
      (node (ref "POT2") (pin "P$6") (pinfunction "P$1_P$6") (pintype "bidirectional"))
      (node (ref "POT3") (pin "1") (pinfunction "1_1") (pintype "bidirectional"))
      (node (ref "POT3") (pin "P$5") (pinfunction "P$1_P$5") (pintype "bidirectional"))
      (node (ref "POT3") (pin "P$6") (pinfunction "P$1_P$6") (pintype "bidirectional"))
      (node (ref "Q301") (pin "2") (pinfunction "E_2") (pintype "passive"))
      (node (ref "Q701") (pin "2") (pinfunction "E_2") (pintype "passive"))
      (node (ref "R302") (pin "2") (pinfunction "2_2") (pintype "passive"))
      (node (ref "R704") (pin "1") (pinfunction "1_1") (pintype "passive"))
      (node (ref "U$1") (pin "2") (pinfunction "GND_2") (pintype "bidirectional"))
      (node (ref "U$2") (pin "3") (pinfunction "3_3") (pintype "passive"))
      (node (ref "U$2") (pin "4") (pinfunction "4_4") (pintype "passive"))
      (node (ref "U$2") (pin "5") (pinfunction "5_5") (pintype "passive"))
      (node (ref "U$2") (pin "6") (pinfunction "6_6") (pintype "passive"))
      (node (ref "U$2") (pin "7") (pinfunction "7_7") (pintype "passive"))
      (node (ref "U$2") (pin "8") (pinfunction "8_8") (pintype "passive"))
      (node (ref "U1") (pin "12") (pinfunction "VSSA_12") (pintype "power_in"))
      (node (ref "U1") (pin "18") (pinfunction "VSS_4_18") (pintype "power_in"))
      (node (ref "U1") (pin "63") (pinfunction "VSS_3_63") (pintype "power_in"))
      (node (ref "ZTT") (pin "P$2") (pinfunction "GND_P$2") (pintype "bidirectional"))
    )
    (net (code "71") (name "Net-(ADC0-PadSW)") (class "Default")
      (node (ref "ADC0") (pin "SW") (pinfunction "SW_SW") (pintype "passive"))
      (node (ref "JP15") (pin "1") (pinfunction "1_1") (pintype "passive"))
    )
    (net (code "72") (name "Net-(ADC0-PadTIP)") (class "Default")
      (node (ref "ADC0") (pin "TIP") (pinfunction "TIP_TIP") (pintype "passive"))
      (node (ref "JP15") (pin "2") (pinfunction "2_2") (pintype "passive"))
    )
    (net (code "73") (name "Net-(ADC1-PadSW)") (class "Default")
      (node (ref "ADC1") (pin "SW") (pinfunction "SW_SW") (pintype "passive"))
      (node (ref "JP16") (pin "1") (pinfunction "1_1") (pintype "passive"))
    )
    (net (code "74") (name "Net-(ADC1-PadTIP)") (class "Default")
      (node (ref "ADC1") (pin "TIP") (pinfunction "TIP_TIP") (pintype "passive"))
      (node (ref "JP16") (pin "2") (pinfunction "2_2") (pintype "passive"))
    )
    (net (code "75") (name "Net-(D101-C1A2)") (class "Default")
      (node (ref "D101") (pin "3") (pinfunction "C1A2_3") (pintype "passive"))
      (node (ref "IC2") (pin "7") (pinfunction "OUT_7") (pintype "output"))
      (node (ref "R102") (pin "2") (pinfunction "2_2") (pintype "passive"))
      (node (ref "R104") (pin "1") (pinfunction "1_1") (pintype "passive"))
    )
    (net (code "76") (name "Net-(D201-C1A2)") (class "Default")
      (node (ref "D201") (pin "3") (pinfunction "C1A2_3") (pintype "passive"))
      (node (ref "IC2") (pin "1") (pinfunction "OUT_1") (pintype "output"))
      (node (ref "R202") (pin "2") (pinfunction "2_2") (pintype "passive"))
      (node (ref "R204") (pin "1") (pinfunction "1_1") (pintype "passive"))
    )
    (net (code "77") (name "Net-(DAC0-PadSW)") (class "Default")
      (node (ref "DAC0") (pin "SW") (pinfunction "SW_SW") (pintype "passive"))
      (node (ref "JP19") (pin "1") (pinfunction "1_1") (pintype "passive"))
    )
    (net (code "78") (name "Net-(DAC0-PadTIP)") (class "Default")
      (node (ref "DAC0") (pin "TIP") (pinfunction "TIP_TIP") (pintype "passive"))
      (node (ref "JP19") (pin "2") (pinfunction "2_2") (pintype "passive"))
    )
    (net (code "79") (name "Net-(DAC1-PadSW)") (class "Default")
      (node (ref "DAC1") (pin "SW") (pinfunction "SW_SW") (pintype "passive"))
      (node (ref "JP20") (pin "1") (pinfunction "1_1") (pintype "passive"))
    )
    (net (code "80") (name "Net-(DAC1-PadTIP)") (class "Default")
      (node (ref "DAC1") (pin "TIP") (pinfunction "TIP_TIP") (pintype "passive"))
      (node (ref "JP20") (pin "2") (pinfunction "2_2") (pintype "passive"))
    )
    (net (code "81") (name "Net-(DGI0-PadSW)") (class "Default")
      (node (ref "DGI0") (pin "SW") (pinfunction "SW_SW") (pintype "passive"))
      (node (ref "JP14") (pin "1") (pinfunction "1_1") (pintype "passive"))
    )
    (net (code "82") (name "Net-(DGI0-PadTIP)") (class "Default")
      (node (ref "DGI0") (pin "TIP") (pinfunction "TIP_TIP") (pintype "passive"))
      (node (ref "JP14") (pin "2") (pinfunction "2_2") (pintype "passive"))
    )
    (net (code "83") (name "Net-(DGO0-PadSW)") (class "Default")
      (node (ref "DGO0") (pin "SW") (pinfunction "SW_SW") (pintype "passive"))
      (node (ref "JP11") (pin "1") (pinfunction "1_1") (pintype "passive"))
    )
    (net (code "84") (name "Net-(DGO0-PadTIP)") (class "Default")
      (node (ref "DGO0") (pin "TIP") (pinfunction "TIP_TIP") (pintype "passive"))
      (node (ref "JP11") (pin "2") (pinfunction "2_2") (pintype "passive"))
    )
    (net (code "85") (name "Net-(F1-Pad1)") (class "Default")
      (node (ref "F1") (pin "1") (pinfunction "1_1") (pintype "bidirectional"))
      (node (ref "U$2") (pin "11") (pinfunction "11_11") (pintype "passive"))
      (node (ref "U$2") (pin "12") (pinfunction "12_12") (pintype "passive"))
    )
    (net (code "86") (name "Net-(F2-Pad1)") (class "Default")
      (node (ref "F2") (pin "1") (pinfunction "1_1") (pintype "bidirectional"))
      (node (ref "U$2") (pin "10") (pinfunction "10_10") (pintype "passive"))
      (node (ref "U$2") (pin "9") (pinfunction "9_9") (pintype "passive"))
    )
    (net (code "87") (name "Net-(F3-Pad1)") (class "Default")
      (node (ref "F3") (pin "1") (pinfunction "1_1") (pintype "bidirectional"))
      (node (ref "U$2") (pin "1") (pinfunction "1_1") (pintype "passive"))
      (node (ref "U$2") (pin "2") (pinfunction "2_2") (pintype "passive"))
    )
    (net (code "88") (name "Net-(IC2A--IN)") (class "Default")
      (node (ref "IC2") (pin "2") (pinfunction "-IN_2") (pintype "input"))
      (node (ref "R201") (pin "2") (pinfunction "2_2") (pintype "passive"))
      (node (ref "R202") (pin "1") (pinfunction "1_1") (pintype "passive"))
      (node (ref "R203") (pin "2") (pinfunction "2_2") (pintype "passive"))
      (node (ref "R205") (pin "2") (pinfunction "2_2") (pintype "passive"))
    )
    (net (code "89") (name "Net-(IC2B--IN)") (class "Default")
      (node (ref "IC2") (pin "6") (pinfunction "-IN_6") (pintype "input"))
      (node (ref "R101") (pin "2") (pinfunction "2_2") (pintype "passive"))
      (node (ref "R102") (pin "1") (pinfunction "1_1") (pintype "passive"))
      (node (ref "R103") (pin "2") (pinfunction "2_2") (pintype "passive"))
      (node (ref "R105") (pin "2") (pinfunction "2_2") (pintype "passive"))
    )
    (net (code "90") (name "Net-(IC3A--IN)") (class "Default")
      (node (ref "IC3") (pin "2") (pinfunction "-IN_2") (pintype "input"))
      (node (ref "R401") (pin "1") (pinfunction "1_1") (pintype "passive"))
      (node (ref "R402") (pin "1") (pinfunction "1_1") (pintype "passive"))
      (node (ref "R403") (pin "1") (pinfunction "1_1") (pintype "passive"))
    )
    (net (code "91") (name "Net-(IC3A-OUT)") (class "Default")
      (node (ref "IC3") (pin "1") (pinfunction "OUT_1") (pintype "output"))
      (node (ref "R402") (pin "2") (pinfunction "2_2") (pintype "passive"))
      (node (ref "R404") (pin "1") (pinfunction "1_1") (pintype "passive"))
    )
    (net (code "92") (name "Net-(IC3B--IN)") (class "Default")
      (node (ref "IC3") (pin "6") (pinfunction "-IN_6") (pintype "input"))
      (node (ref "R501") (pin "1") (pinfunction "1_1") (pintype "passive"))
      (node (ref "R502") (pin "1") (pinfunction "1_1") (pintype "passive"))
      (node (ref "R503") (pin "1") (pinfunction "1_1") (pintype "passive"))
    )
    (net (code "93") (name "Net-(IC3B-OUT)") (class "Default")
      (node (ref "IC3") (pin "7") (pinfunction "OUT_7") (pintype "output"))
      (node (ref "R502") (pin "2") (pinfunction "2_2") (pintype "passive"))
      (node (ref "R504") (pin "1") (pinfunction "1_1") (pintype "passive"))
    )
    (net (code "94") (name "Net-(JP12-Pad1)") (class "Default")
      (node (ref "JP12") (pin "1") (pinfunction "1_1") (pintype "passive"))
      (node (ref "R301") (pin "1") (pinfunction "1_1") (pintype "passive"))
    )
    (net (code "95") (name "Net-(JP13-Pad2)") (class "Default")
      (node (ref "JP13") (pin "2") (pinfunction "2_2") (pintype "passive"))
      (node (ref "R703") (pin "2") (pinfunction "2_2") (pintype "passive"))
      (node (ref "R704") (pin "2") (pinfunction "2_2") (pintype "passive"))
    )
    (net (code "96") (name "Net-(JP17-Pad1)") (class "Default")
      (node (ref "JP17") (pin "1") (pinfunction "1_1") (pintype "passive"))
      (node (ref "R103") (pin "1") (pinfunction "1_1") (pintype "passive"))
    )
    (net (code "97") (name "Net-(JP17-Pad2)") (class "Default")
      (node (ref "JP17") (pin "2") (pinfunction "2_2") (pintype "passive"))
      (node (ref "R203") (pin "1") (pinfunction "1_1") (pintype "passive"))
    )
    (net (code "98") (name "Net-(JP18-Pad1)") (class "Default")
      (node (ref "JP18") (pin "1") (pinfunction "1_1") (pintype "passive"))
      (node (ref "R404") (pin "2") (pinfunction "2_2") (pintype "passive"))
    )
    (net (code "99") (name "Net-(JP18-Pad2)") (class "Default")
      (node (ref "JP18") (pin "2") (pinfunction "2_2") (pintype "passive"))
      (node (ref "R504") (pin "2") (pinfunction "2_2") (pintype "passive"))
    )
    (net (code "100") (name "Net-(POT0-Pad2)") (class "Default")
      (node (ref "POT0") (pin "2") (pinfunction "2_2") (pintype "bidirectional"))
      (node (ref "R201") (pin "1") (pinfunction "1_1") (pintype "passive"))
    )
    (net (code "101") (name "Net-(POT1-Pad2)") (class "Default")
      (node (ref "POT1") (pin "2") (pinfunction "2_2") (pintype "bidirectional"))
      (node (ref "R101") (pin "1") (pinfunction "1_1") (pintype "passive"))
    )
    (net (code "102") (name "Net-(Q301-B)") (class "Default")
      (node (ref "Q301") (pin "1") (pinfunction "B_1") (pintype "passive"))
      (node (ref "R301") (pin "2") (pinfunction "2_2") (pintype "passive"))
      (node (ref "R302") (pin "1") (pinfunction "1_1") (pintype "passive"))
    )
    (net (code "103") (name "Net-(Q701-B)") (class "Default")
      (node (ref "Q701") (pin "1") (pinfunction "B_1") (pintype "passive"))
      (node (ref "R701") (pin "2") (pinfunction "2_2") (pintype "passive"))
    )
    (net (code "104") (name "Net-(Q701-C)") (class "Default")
      (node (ref "Q701") (pin "3") (pinfunction "C_3") (pintype "passive"))
      (node (ref "R702") (pin "2") (pinfunction "2_2") (pintype "passive"))
      (node (ref "R703") (pin "1") (pinfunction "1_1") (pintype "passive"))
    )
    (net (code "105") (name "Net-(U$1-IN)") (class "Default")
      (node (ref "C11") (pin "1") (pinfunction "1_1") (pintype "passive"))
      (node (ref "Q1") (pin "1") (pinfunction "1_1") (pintype "passive"))
      (node (ref "U$1") (pin "1") (pinfunction "IN_1") (pintype "bidirectional"))
      (node (ref "U1") (pin "6") (pinfunction "PD1/OSC=>_6") (pintype "bidirectional"))
      (node (ref "ZTT") (pin "P$3") (pinfunction "OUT_P$3") (pintype "bidirectional"))
    )
    (net (code "106") (name "Net-(U$1-OUT)") (class "Default")
      (node (ref "C12") (pin "1") (pinfunction "1_1") (pintype "passive"))
      (node (ref "Q1") (pin "2") (pinfunction "2_2") (pintype "passive"))
      (node (ref "U$1") (pin "3") (pinfunction "OUT_3") (pintype "bidirectional"))
      (node (ref "U1") (pin "5") (pinfunction "PD0/OSC<=_5") (pintype "bidirectional"))
      (node (ref "ZTT") (pin "P$1") (pinfunction "IN_P$1") (pintype "bidirectional"))
    )
    (net (code "107") (name "Net-(U1J-NRST)") (class "Default")
      (node (ref "R603") (pin "2") (pinfunction "2_2") (pintype "passive"))
      (node (ref "U1") (pin "7") (pinfunction "NRST_7") (pintype "input"))
    )
    (net (code "108") (name "unconnected-(U$2-Pad13)") (class "Default")
      (node (ref "U$2") (pin "13") (pinfunction "13_13") (pintype "passive"))
    )
    (net (code "109") (name "unconnected-(U$2-Pad14)") (class "Default")
      (node (ref "U$2") (pin "14") (pinfunction "14_14") (pintype "passive"))
    )
    (net (code "110") (name "unconnected-(U$2-Pad15)") (class "Default")
      (node (ref "U$2") (pin "15") (pinfunction "15_15") (pintype "passive"))
    )
    (net (code "111") (name "unconnected-(U$2-Pad16)") (class "Default")
      (node (ref "U$2") (pin "16") (pinfunction "16_16") (pintype "passive"))
    )
  )
)
